# Gvove-Piezo_Vibration_Sensor.net
KiCad netlist of a schematic drawn in EAGLE
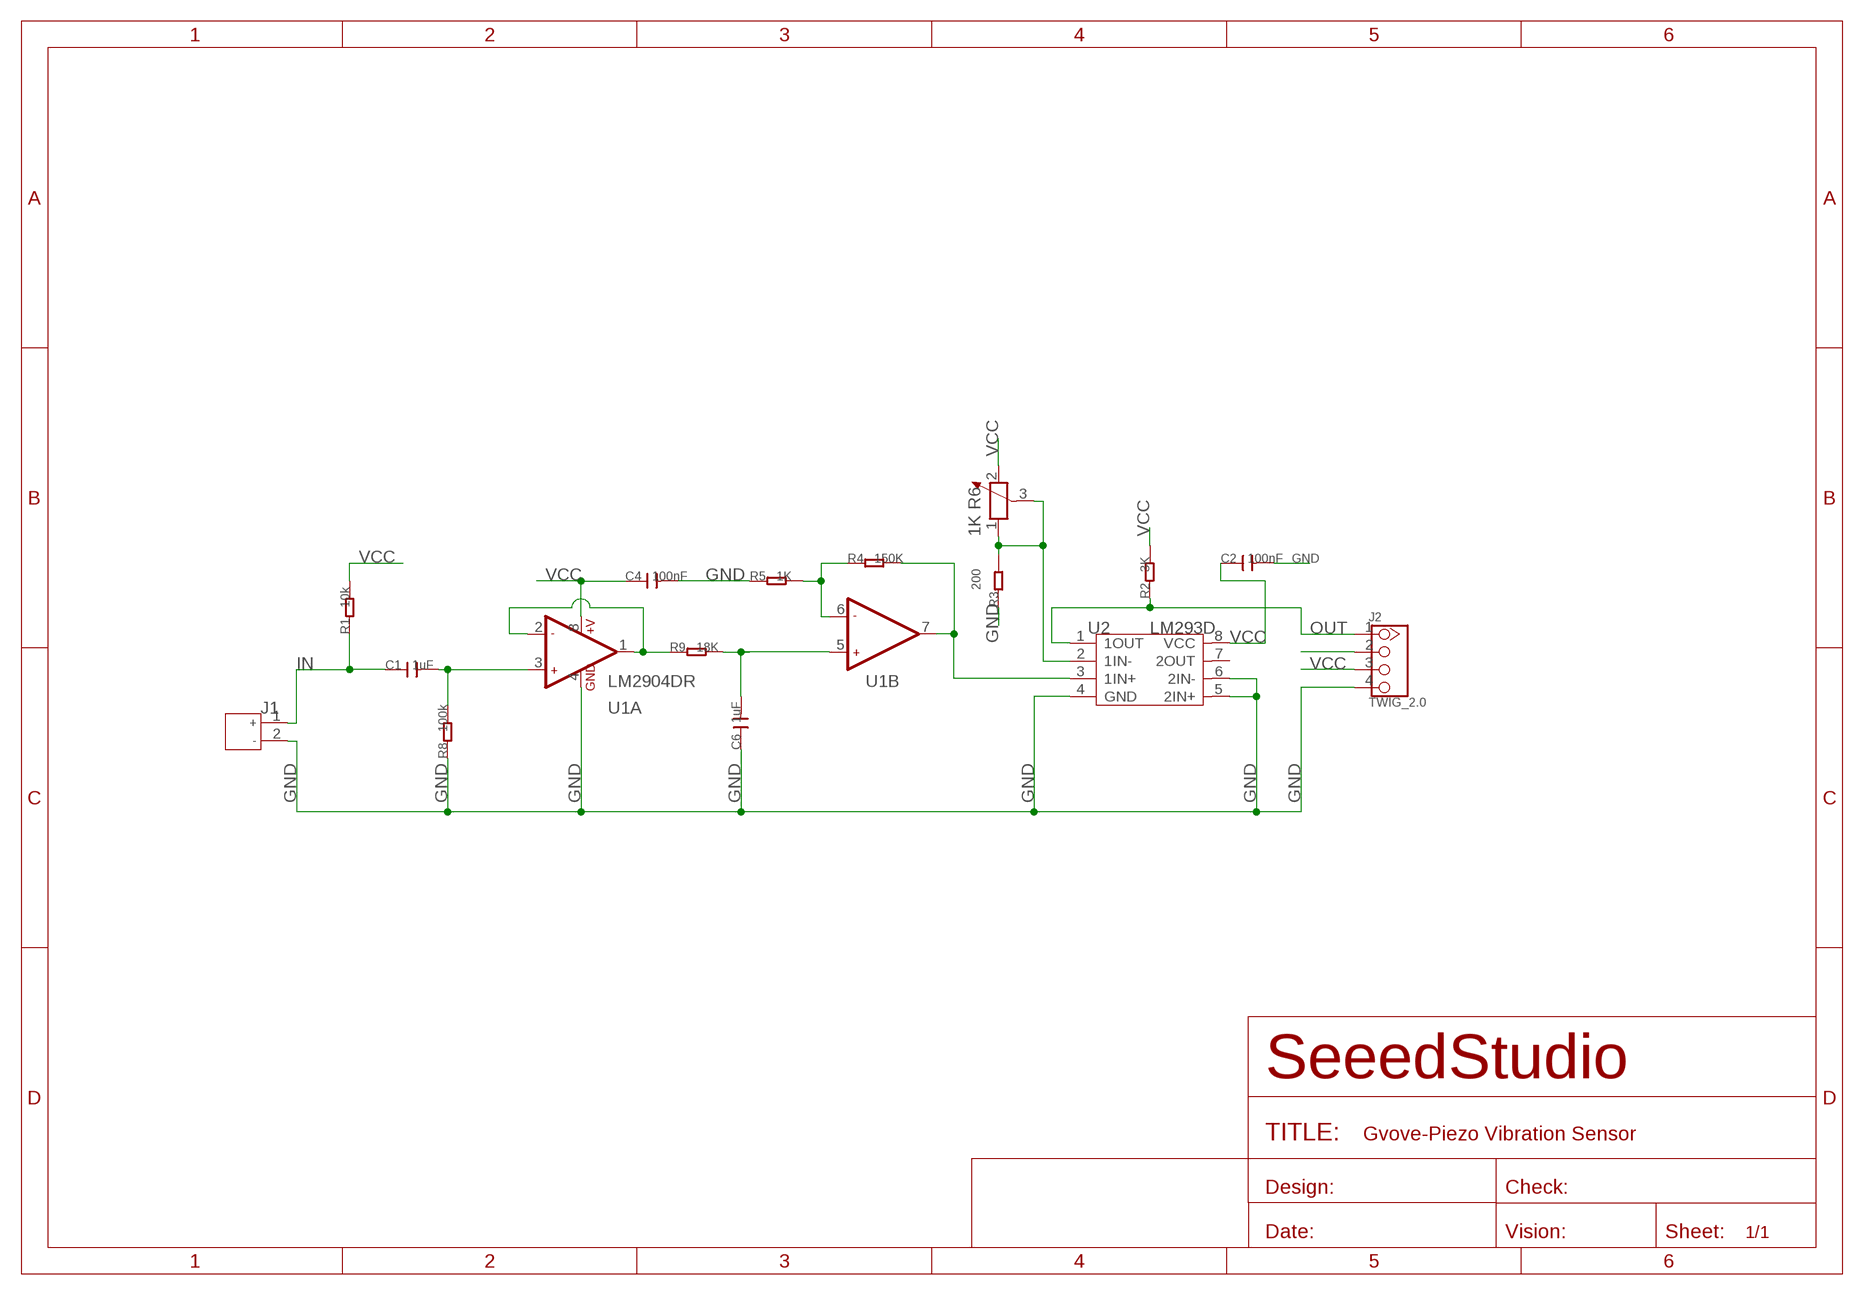
[diagram p0: schematic, sheet 1]

(export (version "E")
  (design (tool "Eeschema 10.0.6"))
  (components
    (comp (ref "C1")
      (value "1uF")
      (footprint "eagle-import:C0603")
      (libsource (lib "eagle-import") (part "C-0603"))
    )
    (comp (ref "C2")
      (value "100nF")
      (footprint "eagle-import:C0603")
      (libsource (lib "eagle-import") (part "C-0603"))
    )
    (comp (ref "C4")
      (value "100nF")
      (footprint "eagle-import:C0603")
      (libsource (lib "eagle-import") (part "C-0603"))
    )
    (comp (ref "C6")
      (value "1uF")
      (footprint "eagle-import:C0603")
      (libsource (lib "eagle-import") (part "C-0603"))
    )
    (comp (ref "J1")
      (value "JACK-JST-2P-PW'2.0'")
      (footprint "eagle-import:JST-2.0")
      (libsource (lib "eagle-import") (part "JACK-JST-2P-PW'2.0'"))
    )
    (comp (ref "J2")
      (value "TWIG_2.0")
      (footprint "eagle-import:2.0_1X4")
      (libsource (lib "eagle-import") (part "TWIG_2.0"))
    )
    (comp (ref "R1")
      (value "10k")
      (footprint "eagle-import:R0603")
      (libsource (lib "eagle-import") (part "R-0603"))
    )
    (comp (ref "R2")
      (value "3K")
      (footprint "eagle-import:R0603")
      (libsource (lib "eagle-import") (part "R-0603"))
    )
    (comp (ref "R3")
      (value "200")
      (footprint "eagle-import:R0603")
      (libsource (lib "eagle-import") (part "R-0603"))
    )
    (comp (ref "R4")
      (value "150K")
      (footprint "eagle-import:R0603")
      (libsource (lib "eagle-import") (part "R-0603"))
    )
    (comp (ref "R5")
      (value "1K")
      (footprint "eagle-import:R0603")
      (libsource (lib "eagle-import") (part "R-0603"))
    )
    (comp (ref "R6")
      (value "1K")
      (footprint "eagle-import:3P-SQUA-7X6.8")
      (libsource (lib "eagle-import") (part "R-POTENTIOMETER'3362'"))
    )
    (comp (ref "R8")
      (value "100k")
      (footprint "eagle-import:R0603")
      (libsource (lib "eagle-import") (part "R-0603"))
    )
    (comp (ref "R9")
      (value "18K")
      (footprint "eagle-import:R0603")
      (libsource (lib "eagle-import") (part "R-0603"))
    )
    (comp (ref "U1")
      (value "LM2904DR")
      (footprint "eagle-import:SO08")
      (libsource (lib "eagle-import") (part "LMV358D"))
    )
    (comp (ref "U2")
      (value "LM293D")
      (footprint "eagle-import:SOIC8-6.0")
      (libsource (lib "eagle-import") (part "LM293D"))
    )
  )
  (nets
    (net (code "1") (name "/GND") (class "Default")
      (node (ref "C2") (pin "2") (pinfunction "2_2") (pintype "passive"))
      (node (ref "C4") (pin "2") (pinfunction "2_2") (pintype "passive"))
      (node (ref "C6") (pin "1") (pinfunction "1_1") (pintype "passive"))
      (node (ref "J1") (pin "2") (pinfunction "P$2_2") (pintype "bidirectional"))
      (node (ref "J2") (pin "4") (pinfunction "4_4") (pintype "bidirectional"))
      (node (ref "R3") (pin "1") (pinfunction "1_1") (pintype "passive"))
      (node (ref "R5") (pin "1") (pinfunction "1_1") (pintype "passive"))
      (node (ref "R8") (pin "1") (pinfunction "1_1") (pintype "passive"))
      (node (ref "U1") (pin "4") (pinfunction "GND_4") (pintype "power_in"))
      (node (ref "U2") (pin "4") (pinfunction "GND_4") (pintype "power_in"))
      (node (ref "U2") (pin "5") (pinfunction "2IN+_5") (pintype "input"))
      (node (ref "U2") (pin "6") (pinfunction "2IN-_6") (pintype "input"))
    )
    (net (code "2") (name "/IN") (class "Default")
      (node (ref "C1") (pin "1") (pinfunction "1_1") (pintype "passive"))
      (node (ref "J1") (pin "1") (pinfunction "P$1_1") (pintype "bidirectional"))
      (node (ref "R1") (pin "1") (pinfunction "1_1") (pintype "passive"))
    )
    (net (code "3") (name "/OUT") (class "Default")
      (node (ref "J2") (pin "1") (pinfunction "1_1") (pintype "bidirectional"))
      (node (ref "R2") (pin "1") (pinfunction "1_1") (pintype "passive"))
      (node (ref "U2") (pin "1") (pinfunction "1OUT_1") (pintype "output"))
    )
    (net (code "4") (name "/VCC") (class "Default")
      (node (ref "C2") (pin "1") (pinfunction "1_1") (pintype "passive"))
      (node (ref "C4") (pin "1") (pinfunction "1_1") (pintype "passive"))
      (node (ref "J2") (pin "3") (pinfunction "3_3") (pintype "bidirectional"))
      (node (ref "R1") (pin "2") (pinfunction "2_2") (pintype "passive"))
      (node (ref "R2") (pin "2") (pinfunction "2_2") (pintype "passive"))
      (node (ref "R6") (pin "2") (pinfunction "2_2") (pintype "passive"))
      (node (ref "U1") (pin "8") (pinfunction "+V_8") (pintype "power_in"))
      (node (ref "U2") (pin "8") (pinfunction "VCC_8") (pintype "power_in"))
    )
    (net (code "5") (name "Net-(U1A-+IN1)") (class "Default")
      (node (ref "C1") (pin "2") (pinfunction "2_2") (pintype "passive"))
      (node (ref "R8") (pin "2") (pinfunction "2_2") (pintype "passive"))
      (node (ref "U1") (pin "3") (pinfunction "+IN1_3") (pintype "input"))
    )
    (net (code "6") (name "Net-(U1A--IN1)") (class "Default")
      (node (ref "R9") (pin "1") (pinfunction "1_1") (pintype "passive"))
      (node (ref "U1") (pin "1") (pinfunction "OUT1_1") (pintype "output"))
      (node (ref "U1") (pin "2") (pinfunction "-IN1_2") (pintype "input"))
    )
    (net (code "7") (name "Net-(U1B-+IN2)") (class "Default")
      (node (ref "C6") (pin "2") (pinfunction "2_2") (pintype "passive"))
      (node (ref "R9") (pin "2") (pinfunction "2_2") (pintype "passive"))
      (node (ref "U1") (pin "5") (pinfunction "+IN2_5") (pintype "input"))
    )
    (net (code "8") (name "Net-(U1B--IN2)") (class "Default")
      (node (ref "R4") (pin "1") (pinfunction "1_1") (pintype "passive"))
      (node (ref "R5") (pin "2") (pinfunction "2_2") (pintype "passive"))
      (node (ref "U1") (pin "6") (pinfunction "-IN2_6") (pintype "input"))
    )
    (net (code "9") (name "Net-(U1B-OUT2)") (class "Default")
      (node (ref "R4") (pin "2") (pinfunction "2_2") (pintype "passive"))
      (node (ref "U1") (pin "7") (pinfunction "OUT2_7") (pintype "output"))
      (node (ref "U2") (pin "3") (pinfunction "1IN+_3") (pintype "input"))
    )
    (net (code "10") (name "Net-(U2-1IN-)") (class "Default")
      (node (ref "R3") (pin "2") (pinfunction "2_2") (pintype "passive"))
      (node (ref "R6") (pin "1") (pinfunction "1_1") (pintype "passive"))
      (node (ref "R6") (pin "3") (pinfunction "3_3") (pintype "passive"))
      (node (ref "U2") (pin "2") (pinfunction "1IN-_2") (pintype "input"))
    )
    (net (code "11") (name "unconnected-(J2-Pad2)") (class "Default")
      (node (ref "J2") (pin "2") (pinfunction "2_2") (pintype "bidirectional"))
    )
    (net (code "12") (name "unconnected-(U2-2OUT-Pad7)") (class "Default")
      (node (ref "U2") (pin "7") (pinfunction "2OUT_7") (pintype "output"))
    )
  )
)
